# POE_PD_5_P-Schalter.net
KiCad netlist of a schematic drawn in EAGLE
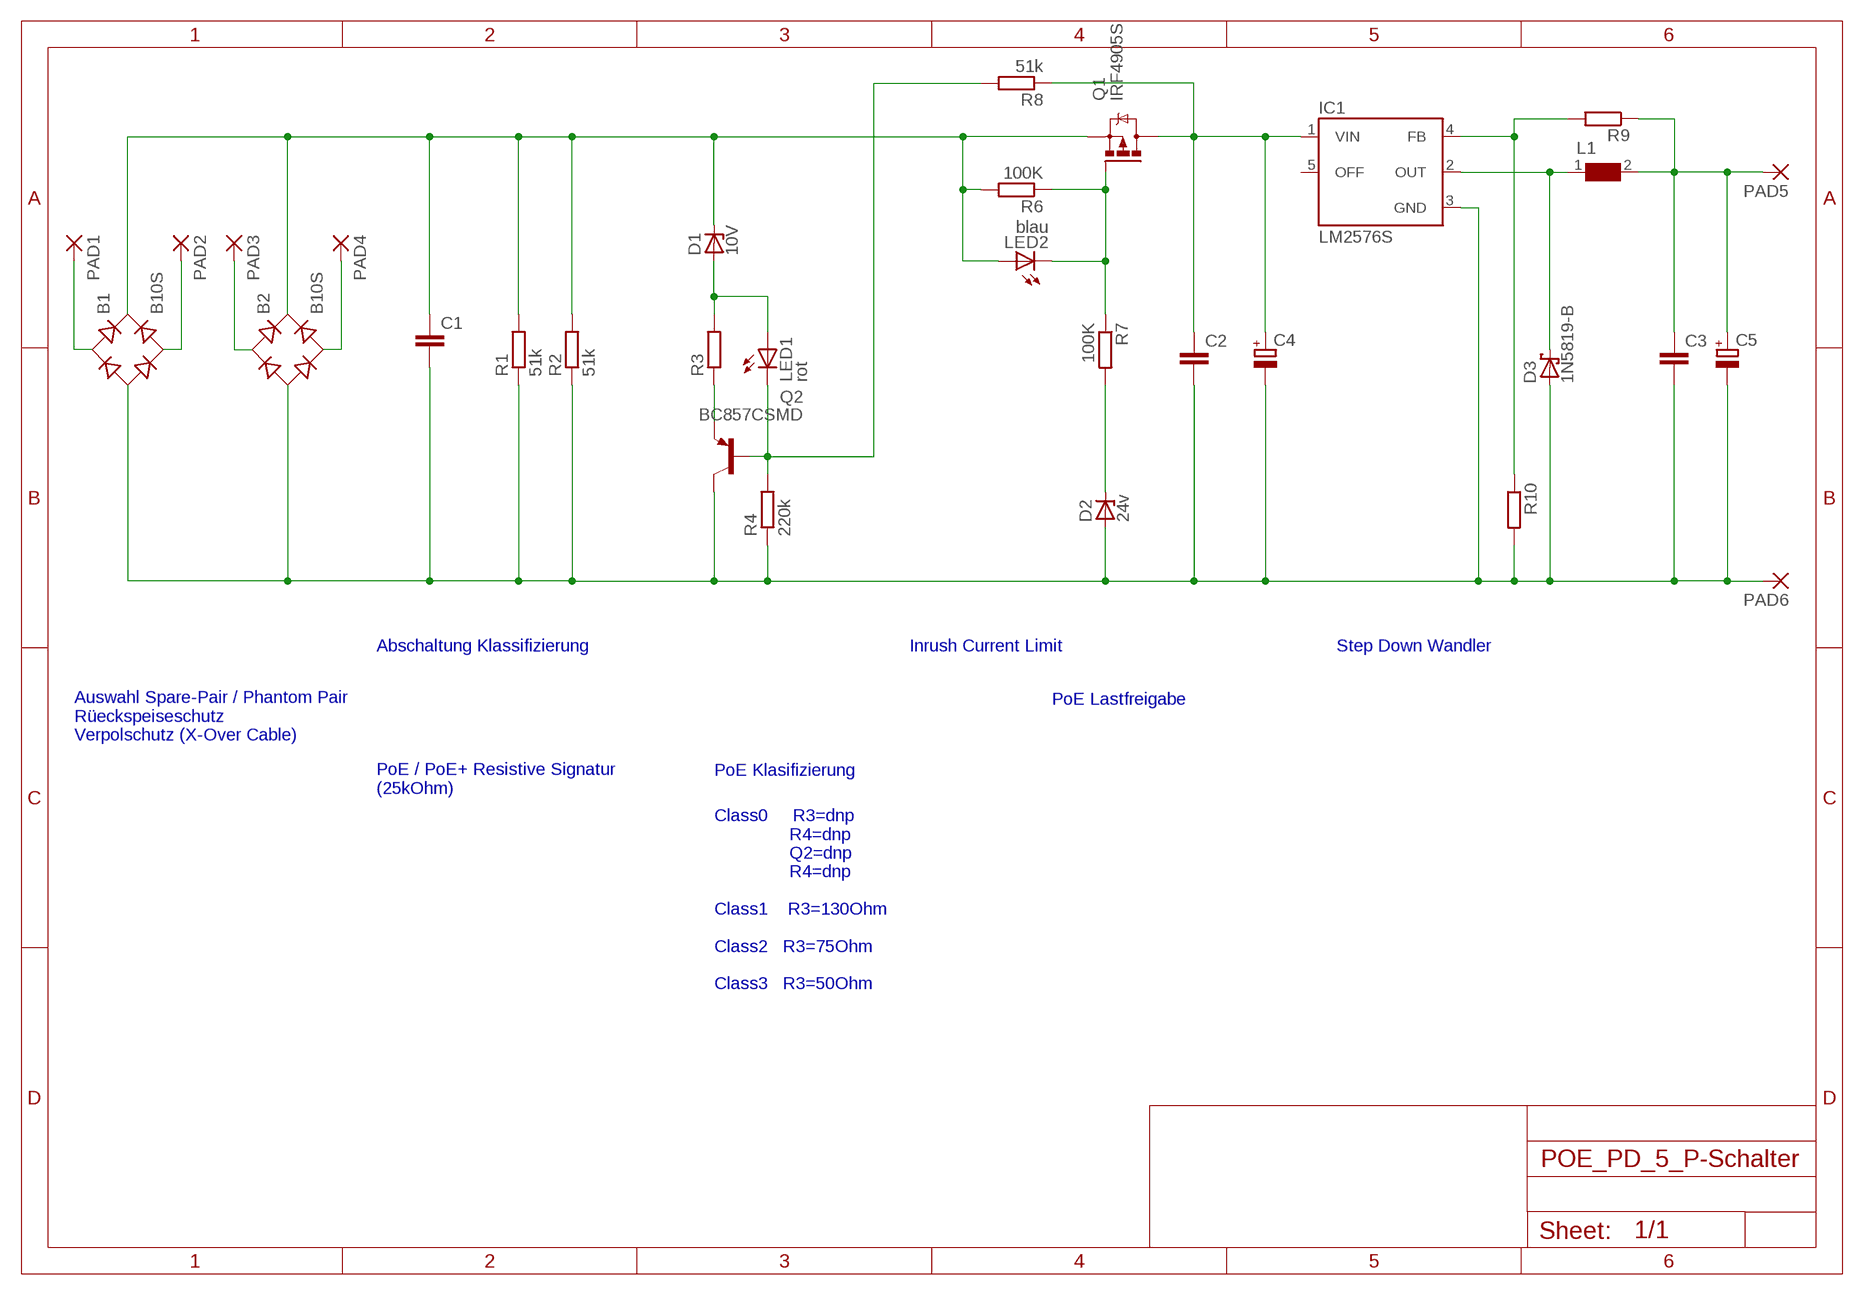
[diagram p0: schematic, sheet 1]

(export (version "E")
  (design (tool "Eeschema 10.0.6"))
  (components
    (comp (ref "B1")
      (value "B10S")
      (footprint "eagle-import:MBS")
      (libsource (lib "eagle-import") (part "BS10"))
    )
    (comp (ref "B2")
      (value "B10S")
      (footprint "eagle-import:MBS")
      (libsource (lib "eagle-import") (part "BS10"))
    )
    (comp (ref "C1")
      (value "C-EUC0805")
      (footprint "eagle-import:C0805")
      (libsource (lib "eagle-import") (part "C-EUC0805"))
    )
    (comp (ref "C2")
      (value "C-EUC0805")
      (footprint "eagle-import:C0805")
      (libsource (lib "eagle-import") (part "C-EUC0805"))
    )
    (comp (ref "C3")
      (value "C-EUC0805")
      (footprint "eagle-import:C0805")
      (libsource (lib "eagle-import") (part "C-EUC0805"))
    )
    (comp (ref "C4")
      (value "CPOL-EU153CLV-0605")
      (footprint "eagle-import:153CLV-0605")
      (libsource (lib "eagle-import") (part "CPOL-EU153CLV-0605"))
    )
    (comp (ref "C5")
      (value "CPOL-EU153CLV-0605")
      (footprint "eagle-import:153CLV-0605")
      (libsource (lib "eagle-import") (part "CPOL-EU153CLV-0605"))
    )
    (comp (ref "D1")
      (value "10V")
      (footprint "eagle-import:SOT23")
      (libsource (lib "eagle-import") (part "ZENER-DIODESOT23"))
    )
    (comp (ref "D2")
      (value "24v")
      (footprint "eagle-import:SOT23")
      (libsource (lib "eagle-import") (part "ZENER-DIODESOT23"))
    )
    (comp (ref "D3")
      (value "1N5819-B")
      (footprint "eagle-import:DO41-7.6")
      (libsource (lib "eagle-import") (part "1N5819-B"))
    )
    (comp (ref "IC1")
      (value "LM2576S")
      (footprint "eagle-import:TO263-5")
      (libsource (lib "eagle-import") (part "LM2576S"))
    )
    (comp (ref "L1")
      (value "WE-PD2_S")
      (footprint "eagle-import:WE-PD2_S")
      (libsource (lib "eagle-import") (part "WE-PD2_S"))
    )
    (comp (ref "LED1")
      (value "rot")
      (footprint "eagle-import:CHIP-LED0805")
      (libsource (lib "eagle-import") (part "LEDCHIP-LED0805"))
    )
    (comp (ref "LED2")
      (value "blau")
      (footprint "eagle-import:CHIP-LED0805")
      (libsource (lib "eagle-import") (part "LEDCHIP-LED0805"))
    )
    (comp (ref "PAD1")
      (value "2,15/1,0")
      (footprint "eagle-import:2,15_1,0")
      (libsource (lib "eagle-import") (part "2,15/1,0"))
    )
    (comp (ref "PAD2")
      (value "2,15/1,0")
      (footprint "eagle-import:2,15_1,0")
      (libsource (lib "eagle-import") (part "2,15/1,0"))
    )
    (comp (ref "PAD3")
      (value "2,15/1,0")
      (footprint "eagle-import:2,15_1,0")
      (libsource (lib "eagle-import") (part "2,15/1,0"))
    )
    (comp (ref "PAD4")
      (value "2,15/1,0")
      (footprint "eagle-import:2,15_1,0")
      (libsource (lib "eagle-import") (part "2,15/1,0"))
    )
    (comp (ref "PAD5")
      (value "2,15/1,0")
      (footprint "eagle-import:2,15_1,0")
      (libsource (lib "eagle-import") (part "2,15/1,0"))
    )
    (comp (ref "PAD6")
      (value "2,15/1,0")
      (footprint "eagle-import:2,15_1,0")
      (libsource (lib "eagle-import") (part "2,15/1,0"))
    )
    (comp (ref "Q1")
      (value "IRF4905S")
      (footprint "eagle-import:D-PAK_TO252AA")
      (libsource (lib "eagle-import") (part "IRF?5305R"))
    )
    (comp (ref "Q2")
      (value "BC857CSMD")
      (footprint "eagle-import:SOT23-BEC")
      (libsource (lib "eagle-import") (part "BC857SMDC"))
    )
    (comp (ref "R1")
      (value "51k")
      (footprint "eagle-import:R0603")
      (libsource (lib "eagle-import") (part "R-EU_R0603"))
    )
    (comp (ref "R2")
      (value "51k")
      (footprint "eagle-import:R0603")
      (libsource (lib "eagle-import") (part "R-EU_R0603"))
    )
    (comp (ref "R3")
      (value "R-EU_R0603")
      (footprint "eagle-import:R0603")
      (libsource (lib "eagle-import") (part "R-EU_R0603"))
    )
    (comp (ref "R4")
      (value "220k")
      (footprint "eagle-import:R0603")
      (libsource (lib "eagle-import") (part "R-EU_R0603"))
    )
    (comp (ref "R6")
      (value "100K")
      (footprint "eagle-import:R0603")
      (libsource (lib "eagle-import") (part "R-EU_R0603"))
    )
    (comp (ref "R7")
      (value "100K")
      (footprint "eagle-import:R0603")
      (libsource (lib "eagle-import") (part "R-EU_R0603"))
    )
    (comp (ref "R8")
      (value "51k")
      (footprint "eagle-import:R0603")
      (libsource (lib "eagle-import") (part "R-EU_R0603"))
    )
    (comp (ref "R9")
      (value "R-EU_R0603")
      (footprint "eagle-import:R0603")
      (libsource (lib "eagle-import") (part "R-EU_R0603"))
    )
    (comp (ref "R10")
      (value "R-EU_R0603")
      (footprint "eagle-import:R0603")
      (libsource (lib "eagle-import") (part "R-EU_R0603"))
    )
  )
  (nets
    (net (code "1") (name "Net-(D1-A)") (class "Default")
      (node (ref "D1") (pin "1") (pinfunction "A_1") (pintype "passive"))
      (node (ref "LED1") (pin "A") (pinfunction "A_A") (pintype "passive"))
      (node (ref "R3") (pin "2") (pinfunction "2_2") (pintype "passive"))
    )
    (net (code "2") (name "Net-(D1-C)") (class "Default")
      (node (ref "B1") (pin "+") (pinfunction "+_+") (pintype "passive"))
      (node (ref "B2") (pin "+") (pinfunction "+_+") (pintype "passive"))
      (node (ref "C1") (pin "1") (pinfunction "1_1") (pintype "passive"))
      (node (ref "D1") (pin "3") (pinfunction "C_3") (pintype "passive"))
      (node (ref "LED2") (pin "A") (pinfunction "A_A") (pintype "passive"))
      (node (ref "Q1") (pin "3") (pinfunction "S_3") (pintype "passive"))
      (node (ref "R1") (pin "2") (pinfunction "2_2") (pintype "passive"))
      (node (ref "R2") (pin "2") (pinfunction "2_2") (pintype "passive"))
      (node (ref "R6") (pin "2") (pinfunction "2_2") (pintype "passive"))
    )
    (net (code "3") (name "Net-(D2-A)") (class "Default")
      (node (ref "B1") (pin "-") (pinfunction "-_-") (pintype "passive"))
      (node (ref "B2") (pin "-") (pinfunction "-_-") (pintype "passive"))
      (node (ref "C1") (pin "2") (pinfunction "2_2") (pintype "passive"))
      (node (ref "C2") (pin "2") (pinfunction "2_2") (pintype "passive"))
      (node (ref "C3") (pin "2") (pinfunction "2_2") (pintype "passive"))
      (node (ref "C4") (pin "-") (pinfunction "-_-") (pintype "passive"))
      (node (ref "C5") (pin "-") (pinfunction "-_-") (pintype "passive"))
      (node (ref "D2") (pin "1") (pinfunction "A_1") (pintype "passive"))
      (node (ref "D3") (pin "A") (pinfunction "A_A") (pintype "passive"))
      (node (ref "IC1") (pin "3") (pinfunction "GND_3") (pintype "power_in"))
      (node (ref "PAD6") (pin "1") (pinfunction "P_1") (pintype "passive"))
      (node (ref "Q2") (pin "C") (pinfunction "C_C") (pintype "passive"))
      (node (ref "R1") (pin "1") (pinfunction "1_1") (pintype "passive"))
      (node (ref "R10") (pin "2") (pinfunction "2_2") (pintype "passive"))
      (node (ref "R2") (pin "1") (pinfunction "1_1") (pintype "passive"))
      (node (ref "R4") (pin "1") (pinfunction "1_1") (pintype "passive"))
    )
    (net (code "4") (name "Net-(D2-C)") (class "Default")
      (node (ref "D2") (pin "3") (pinfunction "C_3") (pintype "passive"))
      (node (ref "R7") (pin "2") (pinfunction "2_2") (pintype "passive"))
    )
    (net (code "5") (name "Net-(IC1-FB)") (class "Default")
      (node (ref "IC1") (pin "4") (pinfunction "FB_4") (pintype "input"))
      (node (ref "R10") (pin "1") (pinfunction "1_1") (pintype "passive"))
      (node (ref "R9") (pin "2") (pinfunction "2_2") (pintype "passive"))
    )
    (net (code "6") (name "Net-(IC1-OUT)") (class "Default")
      (node (ref "D3") (pin "C") (pinfunction "C_C") (pintype "passive"))
      (node (ref "IC1") (pin "2") (pinfunction "OUT_2") (pintype "output"))
      (node (ref "L1") (pin "1") (pinfunction "1_1") (pintype "passive"))
    )
    (net (code "7") (name "Net-(IC1-VIN)") (class "Default")
      (node (ref "C2") (pin "1") (pinfunction "1_1") (pintype "passive"))
      (node (ref "C4") (pin "+") (pinfunction "+_+") (pintype "passive"))
      (node (ref "IC1") (pin "1") (pinfunction "VIN_1") (pintype "power_in"))
      (node (ref "Q1") (pin "4") (pinfunction "D_4") (pintype "passive"))
      (node (ref "R8") (pin "1") (pinfunction "1_1") (pintype "passive"))
    )
    (net (code "8") (name "Net-(LED1-PadC)") (class "Default")
      (node (ref "LED1") (pin "C") (pinfunction "C_C") (pintype "passive"))
      (node (ref "Q2") (pin "B") (pinfunction "B_B") (pintype "passive"))
      (node (ref "R4") (pin "2") (pinfunction "2_2") (pintype "passive"))
      (node (ref "R8") (pin "2") (pinfunction "2_2") (pintype "passive"))
    )
    (net (code "9") (name "Net-(PAD1-P)") (class "Default")
      (node (ref "B1") (pin "AC1") (pinfunction "AC1_AC1") (pintype "passive"))
      (node (ref "PAD1") (pin "1") (pinfunction "P_1") (pintype "passive"))
    )
    (net (code "10") (name "Net-(PAD2-P)") (class "Default")
      (node (ref "B1") (pin "AC2") (pinfunction "AC2_AC2") (pintype "passive"))
      (node (ref "PAD2") (pin "1") (pinfunction "P_1") (pintype "passive"))
    )
    (net (code "11") (name "Net-(PAD3-P)") (class "Default")
      (node (ref "B2") (pin "AC1") (pinfunction "AC1_AC1") (pintype "passive"))
      (node (ref "PAD3") (pin "1") (pinfunction "P_1") (pintype "passive"))
    )
    (net (code "12") (name "Net-(PAD4-P)") (class "Default")
      (node (ref "B2") (pin "AC2") (pinfunction "AC2_AC2") (pintype "passive"))
      (node (ref "PAD4") (pin "1") (pinfunction "P_1") (pintype "passive"))
    )
    (net (code "13") (name "Net-(PAD5-P)") (class "Default")
      (node (ref "C3") (pin "1") (pinfunction "1_1") (pintype "passive"))
      (node (ref "C5") (pin "+") (pinfunction "+_+") (pintype "passive"))
      (node (ref "L1") (pin "2") (pinfunction "2_2") (pintype "passive"))
      (node (ref "PAD5") (pin "1") (pinfunction "P_1") (pintype "passive"))
      (node (ref "R9") (pin "1") (pinfunction "1_1") (pintype "passive"))
    )
    (net (code "14") (name "Net-(Q1-G)") (class "Default")
      (node (ref "LED2") (pin "C") (pinfunction "C_C") (pintype "passive"))
      (node (ref "Q1") (pin "1") (pinfunction "G_1") (pintype "passive"))
      (node (ref "R6") (pin "1") (pinfunction "1_1") (pintype "passive"))
      (node (ref "R7") (pin "1") (pinfunction "1_1") (pintype "passive"))
    )
    (net (code "15") (name "Net-(Q2-PadE)") (class "Default")
      (node (ref "Q2") (pin "E") (pinfunction "E_E") (pintype "passive"))
      (node (ref "R3") (pin "1") (pinfunction "1_1") (pintype "passive"))
    )
    (net (code "16") (name "unconnected-(IC1-OFF-Pad5)") (class "Default")
      (node (ref "IC1") (pin "5") (pinfunction "OFF_5") (pintype "input"))
    )
  )
)
